# classic2mega.net
KiCad netlist of a schematic drawn in EAGLE
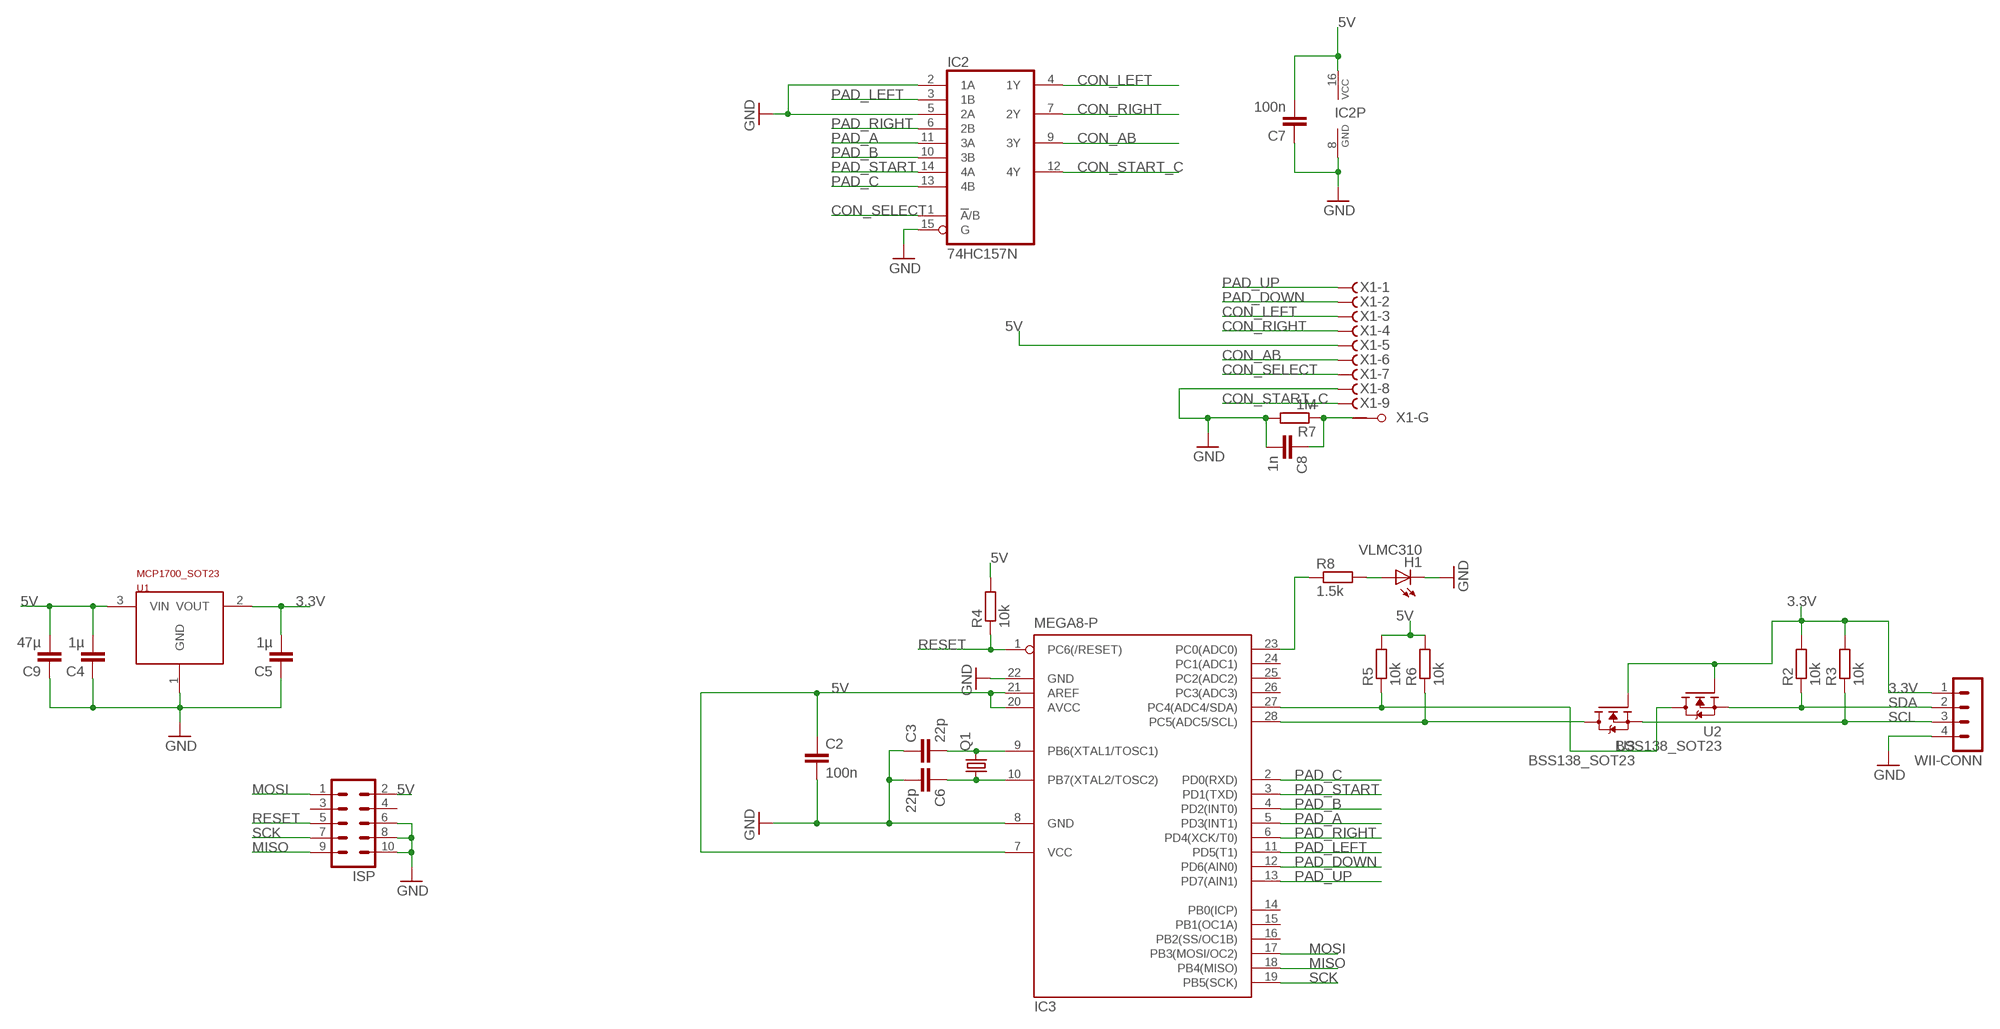
[diagram p0: schematic, sheet 1]

(export (version "E")
  (design (tool "Eeschema 10.0.6"))
  (components
    (comp (ref "C2")
      (value "100n")
      (footprint "eagle-import:C0805K")
      (libsource (lib "eagle-import") (part "C-EUC0805K"))
    )
    (comp (ref "C3")
      (value "22p")
      (footprint "eagle-import:C0805K")
      (libsource (lib "eagle-import") (part "C-EUC0805K"))
    )
    (comp (ref "C4")
      (value "1µ")
      (footprint "eagle-import:C0805K")
      (libsource (lib "eagle-import") (part "C-EUC0805K"))
    )
    (comp (ref "C5")
      (value "1µ")
      (footprint "eagle-import:C0805K")
      (libsource (lib "eagle-import") (part "C-EUC0805K"))
    )
    (comp (ref "C6")
      (value "22p")
      (footprint "eagle-import:C0805K")
      (libsource (lib "eagle-import") (part "C-EUC0805K"))
    )
    (comp (ref "C7")
      (value "100n")
      (footprint "eagle-import:C0805K")
      (libsource (lib "eagle-import") (part "C-EUC0805K"))
    )
    (comp (ref "C8")
      (value "1n")
      (footprint "eagle-import:C0805K")
      (libsource (lib "eagle-import") (part "C-EUC0805K"))
    )
    (comp (ref "C9")
      (value "47µ")
      (footprint "eagle-import:C1210")
      (libsource (lib "eagle-import") (part "resistor_348_C-EUC1210"))
    )
    (comp (ref "H1")
      (value "VLMC310")
      (footprint "eagle-import:PLCC-2")
      (libsource (lib "eagle-import") (part "VLMC310"))
    )
    (comp (ref "IC2")
      (value "74HC157N")
      (footprint "eagle-import:DIL16")
      (libsource (lib "eagle-import") (part "74157NHC"))
    )
    (comp (ref "IC3")
      (value "MEGA8-P")
      (footprint "eagle-import:DIL28-3")
      (libsource (lib "eagle-import") (part "MEGA8-P"))
    )
    (comp (ref "ISP")
      (value "MA05-2")
      (footprint "eagle-import:MA05-2")
      (libsource (lib "eagle-import") (part "MA05-2"))
    )
    (comp (ref "Q1")
      (value "CRYSTALHC49S")
      (footprint "eagle-import:HC49_S")
      (libsource (lib "eagle-import") (part "CRYSTALHC49S"))
    )
    (comp (ref "R2")
      (value "10k")
      (footprint "eagle-import:M0805")
      (libsource (lib "eagle-import") (part "R-EU_M0805"))
    )
    (comp (ref "R3")
      (value "10k")
      (footprint "eagle-import:M0805")
      (libsource (lib "eagle-import") (part "R-EU_M0805"))
    )
    (comp (ref "R4")
      (value "10k")
      (footprint "eagle-import:M0805")
      (libsource (lib "eagle-import") (part "R-EU_M0805"))
    )
    (comp (ref "R5")
      (value "10k")
      (footprint "eagle-import:M0805")
      (libsource (lib "eagle-import") (part "R-EU_M0805"))
    )
    (comp (ref "R6")
      (value "10k")
      (footprint "eagle-import:M0805")
      (libsource (lib "eagle-import") (part "R-EU_M0805"))
    )
    (comp (ref "R7")
      (value "1M")
      (footprint "eagle-import:M0805")
      (libsource (lib "eagle-import") (part "R-EU_M0805"))
    )
    (comp (ref "R8")
      (value "1.5k")
      (footprint "eagle-import:M0805")
      (libsource (lib "eagle-import") (part "R-EU_M0805"))
    )
    (comp (ref "U1")
      (value "MCP1700_SOT23")
      (footprint "eagle-import:SOT23")
      (libsource (lib "eagle-import") (part "MCP1700_SOT23"))
    )
    (comp (ref "U2")
      (value "BSS138_SOT23")
      (footprint "eagle-import:SOT23")
      (libsource (lib "eagle-import") (part "BSS138_SOT23"))
    )
    (comp (ref "U3")
      (value "BSS138_SOT23")
      (footprint "eagle-import:SOT23")
      (libsource (lib "eagle-import") (part "BSS138_SOT23"))
    )
    (comp (ref "WII-CONN")
      (value "MA04-1")
      (footprint "eagle-import:MA04-1")
      (libsource (lib "eagle-import") (part "MA04-1"))
    )
    (comp (ref "X1")
      (value "F09HPS")
      (footprint "eagle-import:F09HP")
      (libsource (lib "eagle-import") (part "F09HPS"))
    )
  )
  (nets
    (net (code "1") (name "/3.3V") (class "Default")
      (node (ref "C5") (pin "2") (pinfunction "2_2") (pintype "passive"))
      (node (ref "R2") (pin "2") (pinfunction "2_2") (pintype "passive"))
      (node (ref "R3") (pin "2") (pinfunction "2_2") (pintype "passive"))
      (node (ref "U1") (pin "2") (pinfunction "VOUT_2") (pintype "bidirectional"))
      (node (ref "U2") (pin "1") (pinfunction "G_1") (pintype "passive"))
      (node (ref "U3") (pin "1") (pinfunction "G_1") (pintype "passive"))
      (node (ref "WII-CONN") (pin "1") (pinfunction "1_1") (pintype "passive"))
    )
    (net (code "2") (name "/5V") (class "Default")
      (node (ref "C2") (pin "1") (pinfunction "1_1") (pintype "passive"))
      (node (ref "C4") (pin "2") (pinfunction "2_2") (pintype "passive"))
      (node (ref "C7") (pin "2") (pinfunction "2_2") (pintype "passive"))
      (node (ref "C9") (pin "2") (pinfunction "2_2") (pintype "passive"))
      (node (ref "IC2") (pin "16") (pinfunction "VCC_16") (pintype "power_in"))
      (node (ref "IC3") (pin "20") (pinfunction "AVCC_20") (pintype "power_in"))
      (node (ref "IC3") (pin "21") (pinfunction "AREF_21") (pintype "passive"))
      (node (ref "IC3") (pin "7") (pinfunction "VCC_7") (pintype "power_in"))
      (node (ref "ISP") (pin "2") (pinfunction "2_2") (pintype "passive"))
      (node (ref "R4") (pin "2") (pinfunction "2_2") (pintype "passive"))
      (node (ref "R5") (pin "2") (pinfunction "2_2") (pintype "passive"))
      (node (ref "R6") (pin "2") (pinfunction "2_2") (pintype "passive"))
      (node (ref "U1") (pin "3") (pinfunction "VIN_3") (pintype "bidirectional"))
      (node (ref "X1") (pin "5") (pinfunction "F_5") (pintype "passive"))
    )
    (net (code "3") (name "/CON_AB") (class "Default")
      (node (ref "IC2") (pin "9") (pinfunction "3Y_9") (pintype "output"))
      (node (ref "X1") (pin "6") (pinfunction "F_6") (pintype "passive"))
    )
    (net (code "4") (name "/CON_LEFT") (class "Default")
      (node (ref "IC2") (pin "4") (pinfunction "1Y_4") (pintype "output"))
      (node (ref "X1") (pin "3") (pinfunction "F_3") (pintype "passive"))
    )
    (net (code "5") (name "/CON_RIGHT") (class "Default")
      (node (ref "IC2") (pin "7") (pinfunction "2Y_7") (pintype "output"))
      (node (ref "X1") (pin "4") (pinfunction "F_4") (pintype "passive"))
    )
    (net (code "6") (name "/CON_SELECT") (class "Default")
      (node (ref "IC2") (pin "1") (pinfunction "~{A}/B_1") (pintype "input"))
      (node (ref "X1") (pin "7") (pinfunction "F_7") (pintype "passive"))
    )
    (net (code "7") (name "/CON_START_C") (class "Default")
      (node (ref "IC2") (pin "12") (pinfunction "4Y_12") (pintype "output"))
      (node (ref "X1") (pin "9") (pinfunction "F_9") (pintype "passive"))
    )
    (net (code "8") (name "/MISO") (class "Default")
      (node (ref "IC3") (pin "18") (pinfunction "PB4(MISO)_18") (pintype "bidirectional"))
      (node (ref "ISP") (pin "9") (pinfunction "9_9") (pintype "passive"))
    )
    (net (code "9") (name "/MOSI") (class "Default")
      (node (ref "IC3") (pin "17") (pinfunction "PB3(MOSI/OC2)_17") (pintype "bidirectional"))
      (node (ref "ISP") (pin "1") (pinfunction "1_1") (pintype "passive"))
    )
    (net (code "10") (name "/PAD_A") (class "Default")
      (node (ref "IC2") (pin "11") (pinfunction "3A_11") (pintype "input"))
      (node (ref "IC3") (pin "5") (pinfunction "PD3(INT1)_5") (pintype "bidirectional"))
    )
    (net (code "11") (name "/PAD_B") (class "Default")
      (node (ref "IC2") (pin "10") (pinfunction "3B_10") (pintype "input"))
      (node (ref "IC3") (pin "4") (pinfunction "PD2(INT0)_4") (pintype "bidirectional"))
    )
    (net (code "12") (name "/PAD_C") (class "Default")
      (node (ref "IC2") (pin "13") (pinfunction "4B_13") (pintype "input"))
      (node (ref "IC3") (pin "2") (pinfunction "PD0(RXD)_2") (pintype "bidirectional"))
    )
    (net (code "13") (name "/PAD_DOWN") (class "Default")
      (node (ref "IC3") (pin "12") (pinfunction "PD6(AIN0)_12") (pintype "bidirectional"))
      (node (ref "X1") (pin "2") (pinfunction "F_2") (pintype "passive"))
    )
    (net (code "14") (name "/PAD_LEFT") (class "Default")
      (node (ref "IC2") (pin "3") (pinfunction "1B_3") (pintype "input"))
      (node (ref "IC3") (pin "11") (pinfunction "PD5(T1)_11") (pintype "bidirectional"))
    )
    (net (code "15") (name "/PAD_RIGHT") (class "Default")
      (node (ref "IC2") (pin "6") (pinfunction "2B_6") (pintype "input"))
      (node (ref "IC3") (pin "6") (pinfunction "PD4(XCK/T0)_6") (pintype "bidirectional"))
    )
    (net (code "16") (name "/PAD_START") (class "Default")
      (node (ref "IC2") (pin "14") (pinfunction "4A_14") (pintype "input"))
      (node (ref "IC3") (pin "3") (pinfunction "PD1(TXD)_3") (pintype "bidirectional"))
    )
    (net (code "17") (name "/PAD_UP") (class "Default")
      (node (ref "IC3") (pin "13") (pinfunction "PD7(AIN1)_13") (pintype "bidirectional"))
      (node (ref "X1") (pin "1") (pinfunction "F_1") (pintype "passive"))
    )
    (net (code "18") (name "/RESET") (class "Default")
      (node (ref "IC3") (pin "1") (pinfunction "PC6(/RESET)_1") (pintype "bidirectional"))
      (node (ref "ISP") (pin "5") (pinfunction "5_5") (pintype "passive"))
      (node (ref "R4") (pin "1") (pinfunction "1_1") (pintype "passive"))
    )
    (net (code "19") (name "/SCK") (class "Default")
      (node (ref "IC3") (pin "19") (pinfunction "PB5(SCK)_19") (pintype "bidirectional"))
      (node (ref "ISP") (pin "7") (pinfunction "7_7") (pintype "passive"))
    )
    (net (code "20") (name "/SCL") (class "Default")
      (node (ref "R3") (pin "1") (pinfunction "1_1") (pintype "passive"))
      (node (ref "U3") (pin "2") (pinfunction "S_2") (pintype "passive"))
      (node (ref "WII-CONN") (pin "3") (pinfunction "3_3") (pintype "passive"))
    )
    (net (code "21") (name "/SDA") (class "Default")
      (node (ref "R2") (pin "1") (pinfunction "1_1") (pintype "passive"))
      (node (ref "U2") (pin "2") (pinfunction "S_2") (pintype "passive"))
      (node (ref "WII-CONN") (pin "2") (pinfunction "2_2") (pintype "passive"))
    )
    (net (code "22") (name "GND") (class "Default")
      (node (ref "C2") (pin "2") (pinfunction "2_2") (pintype "passive"))
      (node (ref "C3") (pin "1") (pinfunction "1_1") (pintype "passive"))
      (node (ref "C4") (pin "1") (pinfunction "1_1") (pintype "passive"))
      (node (ref "C5") (pin "1") (pinfunction "1_1") (pintype "passive"))
      (node (ref "C6") (pin "2") (pinfunction "2_2") (pintype "passive"))
      (node (ref "C7") (pin "1") (pinfunction "1_1") (pintype "passive"))
      (node (ref "C8") (pin "2") (pinfunction "2_2") (pintype "passive"))
      (node (ref "C9") (pin "1") (pinfunction "1_1") (pintype "passive"))
      (node (ref "H1") (pin "C") (pinfunction "C_C") (pintype "passive"))
      (node (ref "IC2") (pin "15") (pinfunction "G_15") (pintype "input"))
      (node (ref "IC2") (pin "2") (pinfunction "1A_2") (pintype "input"))
      (node (ref "IC2") (pin "5") (pinfunction "2A_5") (pintype "input"))
      (node (ref "IC2") (pin "8") (pinfunction "GND_8") (pintype "power_in"))
      (node (ref "IC3") (pin "22") (pinfunction "GND_22") (pintype "power_in"))
      (node (ref "IC3") (pin "8") (pinfunction "GND_8") (pintype "power_in"))
      (node (ref "ISP") (pin "10") (pinfunction "10_10") (pintype "passive"))
      (node (ref "ISP") (pin "6") (pinfunction "6_6") (pintype "passive"))
      (node (ref "ISP") (pin "8") (pinfunction "8_8") (pintype "passive"))
      (node (ref "R7") (pin "2") (pinfunction "2_2") (pintype "passive"))
      (node (ref "U1") (pin "1") (pinfunction "GND_1") (pintype "bidirectional"))
      (node (ref "WII-CONN") (pin "4") (pinfunction "4_4") (pintype "passive"))
      (node (ref "X1") (pin "8") (pinfunction "F_8") (pintype "passive"))
    )
    (net (code "23") (name "Net-(C8-Pad1)") (class "Default")
      (node (ref "C8") (pin "1") (pinfunction "1_1") (pintype "passive"))
      (node (ref "R7") (pin "1") (pinfunction "1_1") (pintype "passive"))
      (node (ref "X1") (pin "G1") (pinfunction "G1_G1") (pintype "passive"))
    )
    (net (code "24") (name "Net-(H1-PadA)") (class "Default")
      (node (ref "H1") (pin "A") (pinfunction "A_A") (pintype "passive"))
      (node (ref "R8") (pin "2") (pinfunction "2_2") (pintype "passive"))
    )
    (net (code "25") (name "Net-(IC3-PB6(XTAL1{slash}TOSC1))") (class "Default")
      (node (ref "C3") (pin "2") (pinfunction "2_2") (pintype "passive"))
      (node (ref "IC3") (pin "9") (pinfunction "PB6(XTAL1/TOSC1)_9") (pintype "bidirectional"))
      (node (ref "Q1") (pin "2") (pinfunction "2_2") (pintype "passive"))
    )
    (net (code "26") (name "Net-(IC3-PB7(XTAL2{slash}TOSC2))") (class "Default")
      (node (ref "C6") (pin "1") (pinfunction "1_1") (pintype "passive"))
      (node (ref "IC3") (pin "10") (pinfunction "PB7(XTAL2/TOSC2)_10") (pintype "bidirectional"))
      (node (ref "Q1") (pin "1") (pinfunction "1_1") (pintype "passive"))
    )
    (net (code "27") (name "Net-(IC3-PC0(ADC0))") (class "Default")
      (node (ref "IC3") (pin "23") (pinfunction "PC0(ADC0)_23") (pintype "bidirectional"))
      (node (ref "R8") (pin "1") (pinfunction "1_1") (pintype "passive"))
    )
    (net (code "28") (name "Net-(IC3-PC4(ADC4{slash}SDA))") (class "Default")
      (node (ref "IC3") (pin "27") (pinfunction "PC4(ADC4/SDA)_27") (pintype "bidirectional"))
      (node (ref "R5") (pin "1") (pinfunction "1_1") (pintype "passive"))
      (node (ref "U2") (pin "3") (pinfunction "D_3") (pintype "passive"))
    )
    (net (code "29") (name "Net-(IC3-PC5(ADC5{slash}SCL))") (class "Default")
      (node (ref "IC3") (pin "28") (pinfunction "PC5(ADC5/SCL)_28") (pintype "bidirectional"))
      (node (ref "R6") (pin "1") (pinfunction "1_1") (pintype "passive"))
      (node (ref "U3") (pin "3") (pinfunction "D_3") (pintype "passive"))
    )
    (net (code "30") (name "unconnected-(IC3-PB0(ICP)-Pad14)") (class "Default")
      (node (ref "IC3") (pin "14") (pinfunction "PB0(ICP)_14") (pintype "bidirectional"))
    )
    (net (code "31") (name "unconnected-(IC3-PB1(OC1A)-Pad15)") (class "Default")
      (node (ref "IC3") (pin "15") (pinfunction "PB1(OC1A)_15") (pintype "bidirectional"))
    )
    (net (code "32") (name "unconnected-(IC3-PB2(SS{slash}OC1B)-Pad16)") (class "Default")
      (node (ref "IC3") (pin "16") (pinfunction "PB2(SS/OC1B)_16") (pintype "bidirectional"))
    )
    (net (code "33") (name "unconnected-(IC3-PC1(ADC1)-Pad24)") (class "Default")
      (node (ref "IC3") (pin "24") (pinfunction "PC1(ADC1)_24") (pintype "bidirectional"))
    )
    (net (code "34") (name "unconnected-(IC3-PC2(ADC2)-Pad25)") (class "Default")
      (node (ref "IC3") (pin "25") (pinfunction "PC2(ADC2)_25") (pintype "bidirectional"))
    )
    (net (code "35") (name "unconnected-(IC3-PC3(ADC3)-Pad26)") (class "Default")
      (node (ref "IC3") (pin "26") (pinfunction "PC3(ADC3)_26") (pintype "bidirectional"))
    )
    (net (code "36") (name "unconnected-(ISP-Pad3)") (class "Default")
      (node (ref "ISP") (pin "3") (pinfunction "3_3") (pintype "passive"))
    )
    (net (code "37") (name "unconnected-(ISP-Pad4)") (class "Default")
      (node (ref "ISP") (pin "4") (pinfunction "4_4") (pintype "passive"))
    )
    (net (code "38") (name "unconnected-(X1-PadG2)") (class "Default")
      (node (ref "X1") (pin "G2") (pinfunction "G2_G2") (pintype "passive"))
    )
  )
)
